# Sheet_1_Main_bord.net
KiCad netlist of a schematic drawn in Altium Designer
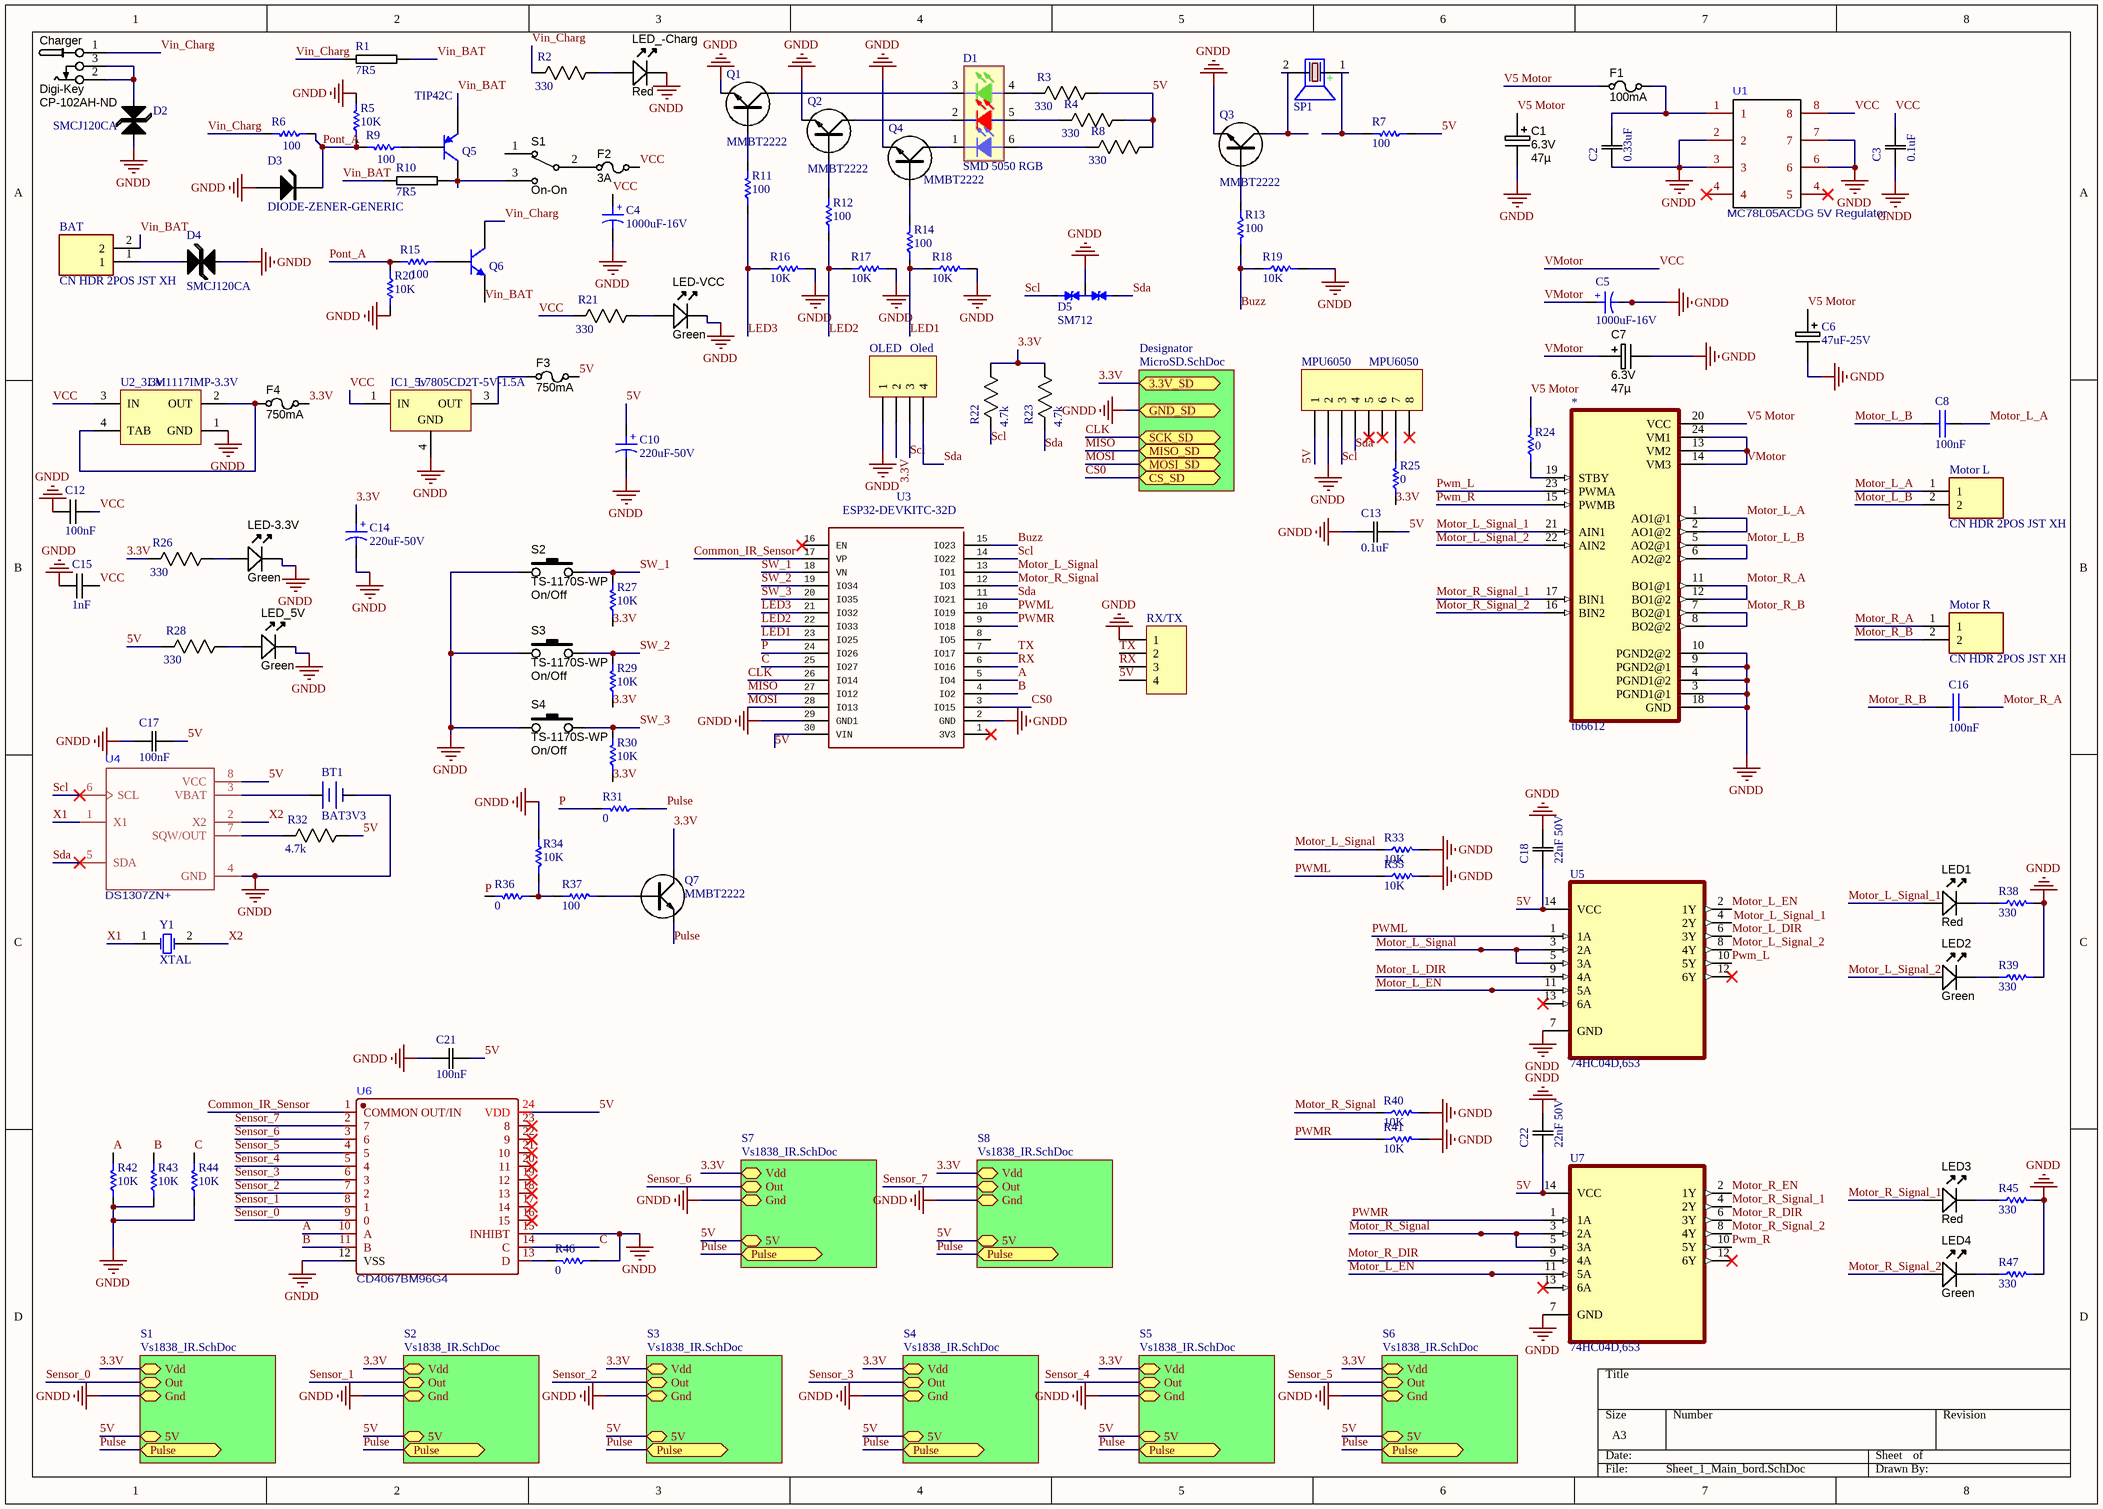
[diagram p0: Sheet_1_Main_bord.SchDoc]

(export (version "E")
  (design (tool "Eeschema 10.0.6"))
  (components
    (comp (ref "*")
      (value "tb6612")
      (footprint "Ssop24_SOP65P760X160-24N")
      (libsource (lib "Schlib_1") (part "tb6612"))
    )
    (comp (ref "BAT")
      (value "CN HDR 2POS JST XH")
      (footprint "JST_B2B-XH-A(LF)(SN)")
      (description "Connector Header Through Hole 2 position 0.098 _2.50mm_\r\nJST XH")
      (fields (field (name "MP") "B2B-XH-A_LF__SN_") (field (name "MF") "JST Sales"))
      (libsource (lib "") (part "CN HDR 2POS JST XH_1"))
    )
    (comp (ref "BT1")
      (value "BAT3V3")
      (footprint "BTH1220")
      (description "Battry Backup")
      (fields (field (name "DESIGNER") "Abbas Basereh"))
      (libsource (lib "Altium") (part "Battry Backup"))
    )
    (comp (ref "C1")
      (value "47µ")
      (footprint "CAPMP3528X210N")
      (description "Capacitor SMD Tantalum 47uF 20% 6.3V 1210")
      (fields (field (name "TOLERANCE") "±20%") (field (name "RATINGS") "6.3V"))
      (libsource (lib "BPL_Library") (part "CAPT_47u_1210_6V3"))
    )
    (comp (ref "C2")
      (value "0.33uF")
      (footprint "0805")
      (description "CAP CER 0.1UF 50V X7R 0805")
      (fields (field (name "TOLERANCE") "10%"))
      (libsource (lib "AltiumLibraries") (part "CAP 470nF 50V"))
    )
    (comp (ref "C3")
      (value "0.1uF")
      (footprint "0805")
      (description "CAP CER 0.1UF 50V X7R 0805")
      (fields (field (name "TOLERANCE") "10%"))
      (libsource (lib "AltiumLibraries") (part "CAP 470nF 50V"))
    )
    (comp (ref "C4")
      (value "1000uF-16V")
      (footprint "CAP SMD 1000UF 16V")
      (description "Cap electrolitic radial")
      (fields (field (name "DESIGNER") "Abbas Basereh"))
      (libsource (lib "Altium") (part "Cap ELECTROLITIC TOTAL SIZE"))
    )
    (comp (ref "C5")
      (value "1000uF-16V")
      (footprint "CAP SMD 1000UF 16V")
      (description "Cap electrolitic radial")
      (fields (field (name "DESIGNER") "Abbas Basereh"))
      (libsource (lib "Altium") (part "Cap ELECTROLITIC TOTAL SIZE"))
    )
    (comp (ref "C6")
      (value "47uF-25V")
      (footprint "PANACAP-D-GENERIC")
      (description "GENERIC CAPACITOR POLARISED")
      (libsource (lib "vh_altium_library") (part "PANACAP-47UF-25V-FK"))
    )
    (comp (ref "C7")
      (value "47µ")
      (footprint "CAPMP3528X210N")
      (description "Capacitor SMD Tantalum 47uF 20% 6.3V 1210")
      (fields (field (name "TOLERANCE") "±20%") (field (name "RATINGS") "6.3V"))
      (libsource (lib "BPL_Library") (part "CAPT_47u_1210_6V3"))
    )
    (comp (ref "C8")
      (value "100nF")
      (footprint "Cap - 100nF - 2")
      (description "Bipolar Capacitor")
      (fields (field (name "VOLTAGE") "100V") (field (name "DESIGNER") "Saeid Jorablo"))
      (libsource (lib "Electrovolt Lib") (part "Cap-Bipolar"))
    )
    (comp (ref "C10")
      (value "220uF-50V")
      (footprint "CAP SMD 1000UF 16V")
      (description "Cap electrolitic radial")
      (fields (field (name "DESIGNER") "Abbas Basereh"))
      (libsource (lib "Altium") (part "Cap ELECTROLITIC TOTAL SIZE"))
    )
    (comp (ref "C12")
      (value "100nF")
      (footprint "1206C-GENERIC")
      (description "CAPACITOR 0603 CERAMIC")
      (libsource (lib "vh_altium_library") (part "1206C-2U2-50V"))
    )
    (comp (ref "C13")
      (value "0.1uF")
      (footprint "0805")
      (description "CAP CER 0.1UF 50V X7R 0805")
      (fields (field (name "TOLERANCE") "10%"))
      (libsource (lib "AltiumLibraries") (part "CAP 470nF 50V"))
    )
    (comp (ref "C14")
      (value "220uF-50V")
      (footprint "CAP SMD 1000UF 16V")
      (description "Cap electrolitic radial")
      (fields (field (name "DESIGNER") "Abbas Basereh"))
      (libsource (lib "Altium") (part "Cap ELECTROLITIC TOTAL SIZE"))
    )
    (comp (ref "C15")
      (value "1nF")
      (footprint "1206C-GENERIC")
      (description "CAPACITOR 0603 CERAMIC")
      (libsource (lib "vh_altium_library") (part "1206C-2U2-50V"))
    )
    (comp (ref "C16")
      (value "100nF")
      (footprint "Cap - 100nF - 2")
      (description "Bipolar Capacitor")
      (fields (field (name "VOLTAGE") "100V") (field (name "DESIGNER") "Saeid Jorablo"))
      (libsource (lib "Electrovolt Lib") (part "Cap-Bipolar"))
    )
    (comp (ref "C17")
      (value "100nF")
      (footprint "0805")
      (description "CAP CER 0.1UF 50V X7R 0805")
      (fields (field (name "TOLERANCE") "10%"))
      (libsource (lib "AltiumLibraries") (part "CAP 470nF 50V"))
    )
    (comp (ref "C18")
      (value "22nF 50V")
      (footprint "0805")
      (description "CAP CER 0.1UF 50V X7R 0805")
      (fields (field (name "TOLERANCE") "10%"))
      (libsource (lib "AltiumLibraries") (part "CAP 470nF 50V"))
    )
    (comp (ref "C21")
      (value "100nF")
      (footprint "0805")
      (description "CAP CER 0.1UF 50V X7R 0805")
      (fields (field (name "TOLERANCE") "10%"))
      (libsource (lib "AltiumLibraries") (part "CAP 470nF 50V"))
    )
    (comp (ref "C22")
      (value "22nF 50V")
      (footprint "0805")
      (description "CAP CER 0.1UF 50V X7R 0805")
      (fields (field (name "TOLERANCE") "10%"))
      (libsource (lib "AltiumLibraries") (part "CAP 470nF 50V"))
    )
    (comp (ref "Charger")
      (value "CONN_PWR_JACK_2.1x5.5mm")
      (footprint "CONN_PWR_JACK_2.1x5.5mm")
      (description "Power Connector, THT, 2.1mm ID, 5.5mm OD")
      (fields (field (name "SUPPLIER 1") "Digi-Key") (field (name "SUPPLIER PART NUMBER 1") "CP-102AH-ND"))
      (libsource (lib "BPL_Library") (part "CONN_PWR_JACK_2.1x5.5mm"))
    )
    (comp (ref "D1")
      (value "probably led colors not mach to real please check the device and change the component")
      (footprint "5050 LED package")
      (description "SMD 5050 RGB LED")
      (fields
        (field (name "COMMENT_1") "SMD 5050 RGB")
        (field (name "DESIGNER") "Abbas Basereh")
        (field (name "PUBLISHER") "Abbas Basereh")
      )
      (libsource (lib "Altium") (part "LED SMD 5050 RGB"))
    )
    (comp (ref "D2")
      (value "SMCJ120CA")
      (footprint "DIODE-SMC")
      (description "Transient Surpression Diode TVS")
      (libsource (lib "vh_altium_library") (part "SMCJ120CA"))
    )
    (comp (ref "D3")
      (value "DIODE-ZENER-GENERIC")
      (footprint "SOT23-DIODE")
      (description "GENERIC ZENER DIODE")
      (libsource (lib "vh_altium_library") (part "DIODE-ZENER-GENERIC"))
    )
    (comp (ref "D4")
      (value "SMCJ120CA")
      (footprint "DIODE-SMC")
      (description "Transient Surpression Diode TVS")
      (libsource (lib "vh_altium_library") (part "SMCJ120CA"))
    )
    (comp (ref "D5")
      (value "SM712")
      (footprint "PSM12___SOT23")
      (description "Asymmetrical TVS Diode for  Extended Common-Mode RS-485")
      (fields (field (name "MANUFACTURER") "SEMTECH") (field (name "MANUFACTURE PART #") "SM712.TC"))
      (libsource (lib "Diode") (part "SM712.TC"))
    )
    (comp (ref "F1")
      (value "100mA")
      (footprint "RESC3216X70N")
      (description "Fuse 160mA 63VDC 1206 SMD")
      (fields (field (name "Comment") "Slow-blow"))
      (libsource (lib "BPL_Library") (part "FUSE_160mA_1206"))
    )
    (comp (ref "F2")
      (value "3A")
      (footprint "RESC3216X70N")
      (description "Fuse 160mA 63VDC 1206 SMD")
      (fields (field (name "Comment") "Slow-blow"))
      (libsource (lib "BPL_Library") (part "FUSE_160mA_1206"))
    )
    (comp (ref "F3")
      (value "750mA")
      (footprint "RESC3216X70N")
      (description "Fuse 160mA 63VDC 1206 SMD")
      (fields (field (name "Comment") "Slow-blow"))
      (libsource (lib "BPL_Library") (part "FUSE_160mA_1206"))
    )
    (comp (ref "F4")
      (value "750mA")
      (footprint "RESC3216X70N")
      (description "Fuse 160mA 63VDC 1206 SMD")
      (fields (field (name "Comment") "Slow-blow"))
      (libsource (lib "BPL_Library") (part "FUSE_160mA_1206"))
    )
    (comp (ref "IC1_5v")
      (value "L7805CD2T-5V-1.5A")
      (footprint "TO-252")
      (description "Precision 500mA Regulator")
      (libsource (lib "Electrovolt Lib") (part "L78M05"))
    )
    (comp (ref "LED-3.3V")
      (value "~")
      (footprint "LED-0805-K")
      (description "LED, 0805 SMD, Green")
      (fields (field (name "COLOR") "Green"))
      (libsource (lib "BPL_Library") (part "LED_SMD_Green_0805_6mcd"))
    )
    (comp (ref "LED-VCC")
      (value "~")
      (footprint "LED-0805-K")
      (description "LED, 0805 SMD, Green")
      (fields (field (name "COLOR") "Green"))
      (libsource (lib "BPL_Library") (part "LED_SMD_Green_0805_6mcd"))
    )
    (comp (ref "LED1")
      (value "~")
      (footprint "LED-0805-K")
      (description "LED 0805 SMD Red 6mcd 621nm")
      (fields (field (name "COLOR") "Red"))
      (libsource (lib "BPL_Library") (part "LED_SMD_Red_0805_6mcd"))
    )
    (comp (ref "LED2")
      (value "~")
      (footprint "LED-0805-K")
      (description "LED, 0805 SMD, Green")
      (fields (field (name "COLOR") "Green"))
      (libsource (lib "BPL_Library") (part "LED_SMD_Green_0805_6mcd"))
    )
    (comp (ref "LED3")
      (value "~")
      (footprint "LED-0805-K")
      (description "LED 0805 SMD Red 6mcd 621nm")
      (fields (field (name "COLOR") "Red"))
      (libsource (lib "BPL_Library") (part "LED_SMD_Red_0805_6mcd"))
    )
    (comp (ref "LED4")
      (value "~")
      (footprint "LED-0805-K")
      (description "LED, 0805 SMD, Green")
      (fields (field (name "COLOR") "Green"))
      (libsource (lib "BPL_Library") (part "LED_SMD_Green_0805_6mcd"))
    )
    (comp (ref "LED_-Charg")
      (value "~")
      (footprint "LED-0805-K")
      (description "LED 0805 SMD Red 6mcd 621nm")
      (fields (field (name "COLOR") "Red"))
      (libsource (lib "BPL_Library") (part "LED_SMD_Red_0805_6mcd"))
    )
    (comp (ref "LED_5V")
      (value "~")
      (footprint "LED-0805-K")
      (description "LED, 0805 SMD, Green")
      (fields (field (name "COLOR") "Green"))
      (libsource (lib "BPL_Library") (part "LED_SMD_Green_0805_6mcd"))
    )
    (comp (ref "Motor L")
      (value "CN HDR 2POS JST XH")
      (footprint "JST_B2B-XH-A(LF)(SN)")
      (description "Connector Header Through Hole 2 position 0.098 _2.50mm_\r\nJST XH")
      (fields (field (name "MP") "B2B-XH-A_LF__SN_") (field (name "MF") "JST Sales"))
      (libsource (lib "AltiumLibraries") (part "CN HDR 2POS JST XH"))
    )
    (comp (ref "Motor R")
      (value "CN HDR 2POS JST XH")
      (footprint "JST_B2B-XH-A(LF)(SN)")
      (description "Connector Header Through Hole 2 position 0.098 _2.50mm_\r\nJST XH")
      (fields (field (name "MP") "B2B-XH-A_LF__SN_") (field (name "MF") "JST Sales"))
      (libsource (lib "AltiumLibraries") (part "CN HDR 2POS JST XH"))
    )
    (comp (ref "MPU6050")
      (value "MPU6050")
      (footprint "HDR1X8")
      (description "Header, 8-Pin")
      (fields (field (name "PUBLISHER") "Altium Limited"))
      (libsource (lib "Altium") (part "Header 8"))
    )
    (comp (ref "OLED")
      (value "Oled")
      (footprint "HDR1X4")
      (description "Header, 4-Pin")
      (fields (field (name "PUBLISHER") "Altium Limited"))
      (libsource (lib "") (part "Header 4_1"))
    )
    (comp (ref "Q1")
      (value "MMBT2222")
      (footprint "SOT23-BCE")
      (description "BC847 SMALL SIGNAL NPN TRANSISTOR")
      (libsource (lib "vh_altium_library") (part "MMBT2222"))
    )
    (comp (ref "Q2")
      (value "MMBT2222")
      (footprint "SOT23-BCE")
      (description "BC847 SMALL SIGNAL NPN TRANSISTOR")
      (libsource (lib "vh_altium_library") (part "MMBT2222"))
    )
    (comp (ref "Q3")
      (value "MMBT2222")
      (footprint "SOT23-BCE")
      (description "BC847 SMALL SIGNAL NPN TRANSISTOR")
      (libsource (lib "vh_altium_library") (part "MMBT2222"))
    )
    (comp (ref "Q4")
      (value "MMBT2222")
      (footprint "SOT23-BCE")
      (description "BC847 SMALL SIGNAL NPN TRANSISTOR")
      (libsource (lib "vh_altium_library") (part "MMBT2222"))
    )
    (comp (ref "Q5")
      (value "TIP42C")
      (footprint "TO-220 AB")
      (description "PNP  power transistor")
      (fields (field (name "MANUFACTURER") "STMicroelectronics") (field (name "DESIGNER") "Abbas Basereh"))
      (libsource (lib "Altium") (part "TIP42C"))
    )
    (comp (ref "Q6")
      (value "TIP41C")
      (footprint "TO-220 AB")
      (description "NPN  power transistor")
      (fields (field (name "MANUFACTURER") "STMicroelectronics") (field (name "DESIGNER") "Abbas Basereh"))
      (libsource (lib "Altium") (part "TIP41C"))
    )
    (comp (ref "Q7")
      (value "MMBT2222")
      (footprint "SOT23-BCE")
      (description "BC847 SMALL SIGNAL NPN TRANSISTOR")
      (libsource (lib "vh_altium_library") (part "MMBT2222"))
    )
    (comp (ref "R1")
      (value "7R5")
      (footprint "2512R-GENERIC")
      (description "GENERIC RESISTOR 2512")
      (fields
        (field (name "MANUFACTURER PART NUMBER") "CRCW25127R50JNEG")
        (field (name "MANUFACTURER") "Vishay/Dale")
      )
      (libsource (lib "vh_altium_library") (part "2512R-7R5"))
    )
    (comp (ref "R2")
      (value "330")
      (footprint "0805")
      (description "RES SMD 1K OHM 1% 1/8W 0603/0805")
      (fields (field (name "TOLERANCE") "1%"))
      (libsource (lib "AltiumLibraries") (part "RES 1k 1/8W - 1%"))
    )
    (comp (ref "R3")
      (value "330")
      (footprint "0805")
      (description "RES SMD 330 OHM 1% 1/8W 0805")
      (fields (field (name "TOLERANCE") "1%"))
      (libsource (lib "AltiumLibraries") (part "RES 330.0 1/8W - 1%"))
    )
    (comp (ref "R4")
      (value "330")
      (footprint "0805")
      (description "RES SMD 330 OHM 1% 1/8W 0805")
      (fields (field (name "TOLERANCE") "1%"))
      (libsource (lib "AltiumLibraries") (part "RES 330.0 1/8W - 1%"))
    )
    (comp (ref "R5")
      (value "10K")
      (footprint "RES 0805 (2012X06L)")
      (description "Resistor")
      (fields (field (name "TOLERANCE") "5%") (field (name "POWER") "1/8 W"))
      (libsource (lib "Electrovolt Lib") (part "Resistor"))
    )
    (comp (ref "R6")
      (value "100")
      (footprint "RES 0805 (2012X06L)")
      (description "Resistor")
      (fields (field (name "TOLERANCE") "5%") (field (name "POWER") "1/8 W"))
      (libsource (lib "Electrovolt Lib") (part "Resistor"))
    )
    (comp (ref "R7")
      (value "100")
      (footprint "RES 0805 (2012X06L)")
      (description "Resistor")
      (fields (field (name "TOLERANCE") "5%") (field (name "POWER") "1/8 W"))
      (libsource (lib "Electrovolt Lib") (part "Resistor"))
    )
    (comp (ref "R8")
      (value "330")
      (footprint "0805")
      (description "RES SMD 330 OHM 1% 1/8W 0805")
      (fields (field (name "TOLERANCE") "1%"))
      (libsource (lib "AltiumLibraries") (part "RES 330.0 1/8W - 1%"))
    )
    (comp (ref "R9")
      (value "100")
      (footprint "RES 0805 (2012X06L)")
      (description "Resistor")
      (fields (field (name "TOLERANCE") "5%") (field (name "POWER") "1/8 W"))
      (libsource (lib "Electrovolt Lib") (part "Resistor"))
    )
    (comp (ref "R10")
      (value "7R5")
      (footprint "2512R-GENERIC")
      (description "GENERIC RESISTOR 2512")
      (fields
        (field (name "MANUFACTURER PART NUMBER") "CRCW25127R50JNEG")
        (field (name "MANUFACTURER") "Vishay/Dale")
      )
      (libsource (lib "vh_altium_library") (part "2512R-7R5"))
    )
    (comp (ref "R11")
      (value "100")
      (footprint "RES 0805 (2012X06L)")
      (description "Resistor")
      (fields (field (name "TOLERANCE") "5%") (field (name "POWER") "1/8 W"))
      (libsource (lib "Electrovolt Lib") (part "Resistor"))
    )
    (comp (ref "R12")
      (value "100")
      (footprint "RES 0805 (2012X06L)")
      (description "Resistor")
      (fields (field (name "TOLERANCE") "5%") (field (name "POWER") "1/8 W"))
      (libsource (lib "Electrovolt Lib") (part "Resistor"))
    )
    (comp (ref "R13")
      (value "100")
      (footprint "RES 0805 (2012X06L)")
      (description "Resistor")
      (fields (field (name "TOLERANCE") "5%") (field (name "POWER") "1/8 W"))
      (libsource (lib "Electrovolt Lib") (part "Resistor"))
    )
    (comp (ref "R14")
      (value "100")
      (footprint "RES 0805 (2012X06L)")
      (description "Resistor")
      (fields (field (name "TOLERANCE") "5%") (field (name "POWER") "1/8 W"))
      (libsource (lib "Electrovolt Lib") (part "Resistor"))
    )
    (comp (ref "R15")
      (value "100")
      (footprint "RES 0805 (2012X06L)")
      (description "Resistor")
      (fields (field (name "TOLERANCE") "5%") (field (name "POWER") "1/8 W"))
      (libsource (lib "Electrovolt Lib") (part "Resistor"))
    )
    (comp (ref "R16")
      (value "10K")
      (footprint "RES 0805 (2012X06L)")
      (description "Resistor")
      (fields (field (name "TOLERANCE") "5%") (field (name "POWER") "1/8 W"))
      (libsource (lib "Electrovolt Lib") (part "Resistor"))
    )
    (comp (ref "R17")
      (value "10K")
      (footprint "RES 0805 (2012X06L)")
      (description "Resistor")
      (fields (field (name "TOLERANCE") "5%") (field (name "POWER") "1/8 W"))
      (libsource (lib "Electrovolt Lib") (part "Resistor"))
    )
    (comp (ref "R18")
      (value "10K")
      (footprint "RES 0805 (2012X06L)")
      (description "Resistor")
      (fields (field (name "TOLERANCE") "5%") (field (name "POWER") "1/8 W"))
      (libsource (lib "Electrovolt Lib") (part "Resistor"))
    )
    (comp (ref "R19")
      (value "10K")
      (footprint "RES 0805 (2012X06L)")
      (description "Resistor")
      (fields (field (name "TOLERANCE") "5%") (field (name "POWER") "1/8 W"))
      (libsource (lib "Electrovolt Lib") (part "Resistor"))
    )
    (comp (ref "R20")
      (value "10K")
      (footprint "RES 0805 (2012X06L)")
      (description "Resistor")
      (fields (field (name "TOLERANCE") "5%") (field (name "POWER") "1/8 W"))
      (libsource (lib "Electrovolt Lib") (part "Resistor"))
    )
    (comp (ref "R21")
      (value "330")
      (footprint "0805")
      (description "RES SMD 330 OHM 1% 1/8W 0805")
      (fields (field (name "TOLERANCE") "1%"))
      (libsource (lib "AltiumLibraries") (part "RES 330.0 1/8W - 1%"))
    )
    (comp (ref "R22")
      (value "4.7k")
      (footprint "0805")
      (description "RES SMD 4.7k OHM 5% 1/8W 0805")
      (fields (field (name "TOLERANCE") "5%"))
      (libsource (lib "AltiumLibraries") (part "RES 4.7k 1/8W - 5%"))
    )
    (comp (ref "R23")
      (value "4.7k")
      (footprint "0805")
      (description "RES SMD 4.7k OHM 5% 1/8W 0805")
      (fields (field (name "TOLERANCE") "5%"))
      (libsource (lib "AltiumLibraries") (part "RES 4.7k 1/8W - 5%"))
    )
    (comp (ref "R24")
      (value "0")
      (footprint "SMD_RES_0805")
      (description "Resistor")
      (fields (field (name "TOLERANCE") "5%") (field (name "POWER") "1/8 W"))
      (libsource (lib "Electrovolt Lib") (part "Resistor"))
    )
    (comp (ref "R25")
      (value "0")
      (footprint "SMD_RES_0805")
      (description "Resistor")
      (fields (field (name "TOLERANCE") "5%") (field (name "POWER") "1/8 W"))
      (libsource (lib "Electrovolt Lib") (part "Resistor"))
    )
    (comp (ref "R26")
      (value "330")
      (footprint "0805")
      (description "RES SMD 330 OHM 1% 1/8W 0805")
      (fields (field (name "TOLERANCE") "1%"))
      (libsource (lib "AltiumLibraries") (part "RES 330.0 1/8W - 1%"))
    )
    (comp (ref "R27")
      (value "10K")
      (footprint "RES 0805 (2012X06L)")
      (description "Resistor")
      (fields (field (name "TOLERANCE") "5%") (field (name "POWER") "1/8 W"))
      (libsource (lib "Electrovolt Lib") (part "Resistor"))
    )
    (comp (ref "R28")
      (value "330")
      (footprint "0805")
      (description "RES SMD 330 OHM 1% 1/8W 0805")
      (fields (field (name "TOLERANCE") "1%"))
      (libsource (lib "AltiumLibraries") (part "RES 330.0 1/8W - 1%"))
    )
    (comp (ref "R29")
      (value "10K")
      (footprint "RES 0805 (2012X06L)")
      (description "Resistor")
      (fields (field (name "TOLERANCE") "5%") (field (name "POWER") "1/8 W"))
      (libsource (lib "Electrovolt Lib") (part "Resistor"))
    )
    (comp (ref "R30")
      (value "10K")
      (footprint "RES 0805 (2012X06L)")
      (description "Resistor")
      (fields (field (name "TOLERANCE") "5%") (field (name "POWER") "1/8 W"))
      (libsource (lib "Electrovolt Lib") (part "Resistor"))
    )
    (comp (ref "R31")
      (value "0")
      (footprint "RES 0805 (2012X06L)")
      (description "Resistor")
      (fields (field (name "TOLERANCE") "5%") (field (name "POWER") "1/8 W"))
      (libsource (lib "Electrovolt Lib") (part "Resistor"))
    )
    (comp (ref "R32")
      (value "4.7k")
      (footprint "0805")
      (description "RES SMD 4.7k OHM 5% 1/8W 0805")
      (fields (field (name "TOLERANCE") "5%"))
      (libsource (lib "AltiumLibraries") (part "RES 4.7k 1/8W - 5%"))
    )
    (comp (ref "R33")
      (value "10K")
      (footprint "RES 0805 (2012X06L)")
      (description "Resistor")
      (fields (field (name "TOLERANCE") "5%") (field (name "POWER") "1/8 W"))
      (libsource (lib "Electrovolt Lib") (part "Resistor"))
    )
    (comp (ref "R34")
      (value "10K")
      (footprint "RES 0805 (2012X06L)")
      (description "Resistor")
      (fields (field (name "TOLERANCE") "5%") (field (name "POWER") "1/8 W"))
      (libsource (lib "Electrovolt Lib") (part "Resistor"))
    )
    (comp (ref "R35")
      (value "10K")
      (footprint "RES 0805 (2012X06L)")
      (description "Resistor")
      (fields (field (name "TOLERANCE") "5%") (field (name "POWER") "1/8 W"))
      (libsource (lib "Electrovolt Lib") (part "Resistor"))
    )
    (comp (ref "R36")
      (value "0")
      (footprint "RES 0805 (2012X06L)")
      (description "Resistor")
      (fields (field (name "TOLERANCE") "5%") (field (name "POWER") "1/8 W"))
      (libsource (lib "Electrovolt Lib") (part "Resistor"))
    )
    (comp (ref "R37")
      (value "100")
      (footprint "RES 0805 (2012X06L)")
      (description "Resistor")
      (fields (field (name "TOLERANCE") "5%") (field (name "POWER") "1/8 W"))
      (libsource (lib "Electrovolt Lib") (part "Resistor"))
    )
    (comp (ref "R38")
      (value "330")
      (footprint "RES 0805 (2012X06L)")
      (description "Resistor")
      (fields (field (name "TOLERANCE") "5%") (field (name "POWER") "1/8 W"))
      (libsource (lib "Electrovolt Lib") (part "Resistor"))
    )
    (comp (ref "R39")
      (value "330")
      (footprint "RES 0805 (2012X06L)")
      (description "Resistor")
      (fields (field (name "TOLERANCE") "5%") (field (name "POWER") "1/8 W"))
      (libsource (lib "Electrovolt Lib") (part "Resistor"))
    )
    (comp (ref "R40")
      (value "10K")
      (footprint "RES 0805 (2012X06L)")
      (description "Resistor")
      (fields (field (name "TOLERANCE") "5%") (field (name "POWER") "1/8 W"))
      (libsource (lib "Electrovolt Lib") (part "Resistor"))
    )
    (comp (ref "R41")
      (value "10K")
      (footprint "RES 0805 (2012X06L)")
      (description "Resistor")
      (fields (field (name "TOLERANCE") "5%") (field (name "POWER") "1/8 W"))
      (libsource (lib "Electrovolt Lib") (part "Resistor"))
    )
    (comp (ref "R42")
      (value "10K")
      (footprint "RES 0805 (2012X06L)")
      (description "Resistor")
      (fields (field (name "TOLERANCE") "5%") (field (name "POWER") "1/8 W"))
      (libsource (lib "Electrovolt Lib") (part "Resistor"))
    )
    (comp (ref "R43")
      (value "10K")
      (footprint "RES 0805 (2012X06L)")
      (description "Resistor")
      (fields (field (name "TOLERANCE") "5%") (field (name "POWER") "1/8 W"))
      (libsource (lib "Electrovolt Lib") (part "Resistor"))
    )
    (comp (ref "R44")
      (value "10K")
      (footprint "RES 0805 (2012X06L)")
      (description "Resistor")
      (fields (field (name "TOLERANCE") "5%") (field (name "POWER") "1/8 W"))
      (libsource (lib "Electrovolt Lib") (part "Resistor"))
    )
    (comp (ref "R45")
      (value "330")
      (footprint "RES 0805 (2012X06L)")
      (description "Resistor")
      (fields (field (name "TOLERANCE") "5%") (field (name "POWER") "1/8 W"))
      (libsource (lib "Electrovolt Lib") (part "Resistor"))
    )
    (comp (ref "R46")
      (value "0")
      (footprint "RES 0805 (2012X06L)")
      (description "Resistor")
      (fields (field (name "TOLERANCE") "5%") (field (name "POWER") "1/8 W"))
      (libsource (lib "Electrovolt Lib") (part "Resistor"))
    )
    (comp (ref "R47")
      (value "330")
      (footprint "RES 0805 (2012X06L)")
      (description "Resistor")
      (fields (field (name "TOLERANCE") "5%") (field (name "POWER") "1/8 W"))
      (libsource (lib "Electrovolt Lib") (part "Resistor"))
    )
    (comp (ref "RX/TX")
      (value "~")
      (footprint "HDR1X4")
      (description "Header, 4-Pin")
      (fields (field (name "PUBLISHER") "Altium Limited"))
      (libsource (lib "Altium") (part "Header 4"))
    )
    (comp (ref "S1")
      (value "ON-ON")
      (footprint "SWITCH_SPDT_SLIDER")
      (description "Switch THD vertical toggle SPDT")
      (fields (field (name "SWITCH FUNCTION") "On-On"))
      (libsource (lib "BPL_Library") (part "SW_THD_SPDT_On-On"))
    )
    (comp (ref "S2")
      (value "TS-1170S-WP")
      (footprint "TS-1170S")
      (description "Switch SMD Tact 7.0mm Stem")
      (fields (field (name "FUNCTION") "On/Off"))
      (libsource (lib "BPL_Library") (part "SW_SMD_PB_7.0mm"))
    )
    (comp (ref "S3")
      (value "TS-1170S-WP")
      (footprint "TS-1170S")
      (description "Switch SMD Tact 7.0mm Stem")
      (fields (field (name "FUNCTION") "On/Off"))
      (libsource (lib "BPL_Library") (part "SW_SMD_PB_7.0mm"))
    )
    (comp (ref "S4")
      (value "TS-1170S-WP")
      (footprint "TS-1170S")
      (description "Switch SMD Tact 7.0mm Stem")
      (fields (field (name "FUNCTION") "On/Off"))
      (libsource (lib "BPL_Library") (part "SW_SMD_PB_7.0mm"))
    )
    (comp (ref "SP1")
      (value "~")
      (footprint "BUZZER 7.62mm DC")
      (description "PIEZO BUZZER ACTIVE")
      (fields (field (name "DESIGNER") "Abbas Basereh") (field (name "PUBLISHER") "Abbas Basereh"))
      (libsource (lib "Altium") (part "PIEZO BUZZER"))
    )
    (comp (ref "U1")
      (value "MC78L05ACDG 5V Regulator")
      (footprint "78L05CD15V5V_LIB")
      (libsource (lib "Schlib_1") (part "MC78L05ACDG 5V Regulator"))
    )
    (comp (ref "U2_3.3v")
      (value "LM1117IMP-3.3V")
      (footprint "TO-252")
      (description "x.x Volt, 800mA Low-Dropout Linear Regulator, 4-pin SOT-223")
      (fields
        (field (name "PARTNUMBER") "LM1117IMP-3.3")
        (field (name "MANUFACTURER") "National Semiconductor")
        (field (name "PUBLISHER") "Altium Limited")
      )
      (libsource (lib "Electrovolt Lib") (part "LM1117IMP-x.x"))
    )
    (comp (ref "U3")
      (value "ESP32-DEVKITC-32D")
      (footprint "MODULE_ESP32-DEVKITV1")
      (description "Eval Board For Esp-Wroom-32")
      (fields (field (name "MF") "Espressif Systems"))
      (libsource (lib "Integrated_Library12") (part "ESP32-DEVKITC-32D"))
    )
    (comp (ref "U4") (value "DS1307ZN+") (footprint "SOIC-8") (libsource (lib "Schlib_1") (part "DS1307ZN+")))
    (comp (ref "U5")
      (value "74HC04D,653")
      (footprint "SOIC127P600X175-14AN")
      (description "Inverter IC 6 Channel 14-SO")
      (fields (field (name "MF") "Nexperia USA"))
      (libsource (lib "74HC04D_653") (part "74HC04D,653"))
    )
    (comp (ref "U6")
      (value "CD4067BM96G4")
      (footprint "CD4067BM_SOIC-24")
      (libsource (lib "Schlib_1") (part "CD4067BM96G4"))
    )
    (comp (ref "U7")
      (value "74HC04D,653")
      (footprint "SOIC127P600X175-14AN")
      (description "Inverter IC 6 Channel 14-SO")
      (fields (field (name "MF") "Nexperia USA"))
      (libsource (lib "74HC04D_653") (part "74HC04D,653"))
    )
    (comp (ref "Y1")
      (value "XTAL")
      (footprint "R38")
      (description "Crystal Oscillator")
      (fields (field (name "PUBLISHER") "Altium Limited"))
      (libsource (lib "Miscellaneous Devices") (part "XTAL"))
    )
  )
  (nets
    (net (code "1") (name "/3.3V") (class "Default")
      (node (ref "C14") (pin "1") (pinfunction "1_1") (pintype "passive"))
      (node (ref "F4") (pin "1") (pinfunction "1_1") (pintype "passive"))
      (node (ref "OLED") (pin "2") (pinfunction "2_2") (pintype "passive"))
      (node (ref "Q7") (pin "C") (pintype "passive"))
      (node (ref "R22") (pin "1") (pinfunction "R1_1") (pintype "passive"))
      (node (ref "R23") (pin "1") (pinfunction "R1_1") (pintype "passive"))
      (node (ref "R25") (pin "1") (pinfunction "1_1") (pintype "passive"))
      (node (ref "R26") (pin "2") (pinfunction "R2_2") (pintype "passive"))
      (node (ref "R27") (pin "1") (pinfunction "1_1") (pintype "passive"))
      (node (ref "R29") (pin "1") (pinfunction "1_1") (pintype "passive"))
      (node (ref "R30") (pin "1") (pinfunction "1_1") (pintype "passive"))
    )
    (net (code "2") (name "/5V") (class "Default")
      (node (ref "C10") (pin "1") (pinfunction "1_1") (pintype "passive"))
      (node (ref "C13") (pin "2") (pinfunction "C2_2") (pintype "passive"))
      (node (ref "C17") (pin "2") (pinfunction "C2_2") (pintype "passive"))
      (node (ref "C18") (pin "1") (pinfunction "C1_1") (pintype "passive"))
      (node (ref "C21") (pin "2") (pinfunction "C2_2") (pintype "passive"))
      (node (ref "C22") (pin "1") (pinfunction "C1_1") (pintype "passive"))
      (node (ref "F3") (pin "1") (pinfunction "1_1") (pintype "passive"))
      (node (ref "MPU6050") (pin "1") (pinfunction "1_1") (pintype "passive"))
      (node (ref "R28") (pin "2") (pinfunction "R2_2") (pintype "passive"))
      (node (ref "R3") (pin "1") (pinfunction "R1_1") (pintype "passive"))
      (node (ref "R32") (pin "1") (pinfunction "R1_1") (pintype "passive"))
      (node (ref "R4") (pin "1") (pinfunction "R1_1") (pintype "passive"))
      (node (ref "R7") (pin "1") (pinfunction "1_1") (pintype "passive"))
      (node (ref "R8") (pin "1") (pinfunction "R1_1") (pintype "passive"))
      (node (ref "RX/TX") (pin "4") (pinfunction "4_4") (pintype "passive"))
      (node (ref "U3") (pin "30") (pinfunction "VIN_30") (pintype "passive"))
      (node (ref "U4") (pin "8") (pinfunction "VCC_8") (pintype "passive"))
      (node (ref "U5") (pin "14") (pinfunction "VCC_14") (pintype "power_in"))
      (node (ref "U6") (pin "24") (pinfunction "VDD_24") (pintype "passive"))
      (node (ref "U7") (pin "14") (pinfunction "VCC_14") (pintype "power_in"))
    )
    (net (code "3") (name "/A") (class "Default")
      (node (ref "R42") (pin "2") (pinfunction "2_2") (pintype "passive"))
      (node (ref "U3") (pin "5") (pinfunction "IO4_5") (pintype "passive"))
      (node (ref "U6") (pin "10") (pinfunction "A_10") (pintype "passive"))
    )
    (net (code "4") (name "/B") (class "Default")
      (node (ref "R43") (pin "2") (pinfunction "2_2") (pintype "passive"))
      (node (ref "U3") (pin "4") (pinfunction "IO2_4") (pintype "passive"))
      (node (ref "U6") (pin "11") (pinfunction "B_11") (pintype "passive"))
    )
    (net (code "5") (name "/Buzz") (class "Default")
      (node (ref "R13") (pin "2") (pinfunction "2_2") (pintype "passive"))
      (node (ref "R19") (pin "1") (pinfunction "1_1") (pintype "passive"))
      (node (ref "U3") (pin "15") (pinfunction "IO23_15") (pintype "passive"))
    )
    (net (code "6") (name "/C") (class "Default")
      (node (ref "R44") (pin "2") (pinfunction "2_2") (pintype "passive"))
      (node (ref "U3") (pin "25") (pinfunction "IO27_25") (pintype "passive"))
      (node (ref "U6") (pin "14") (pinfunction "C_14") (pintype "passive"))
    )
    (net (code "7") (name "/CLK") (class "Default")
      (node (ref "U3") (pin "26") (pinfunction "IO14_26") (pintype "passive"))
    )
    (net (code "8") (name "/CS0") (class "Default")
      (node (ref "U3") (pin "3") (pinfunction "IO15_3") (pintype "passive"))
    )
    (net (code "9") (name "/Common_IR_Sensor") (class "Default")
      (node (ref "U3") (pin "17") (pinfunction "VP_17") (pintype "passive"))
      (node (ref "U6") (pin "1") (pinfunction "COMMON_OUT/IN_1") (pintype "passive"))
    )
    (net (code "10") (name "/LED1") (class "Default")
      (node (ref "R14") (pin "1") (pinfunction "1_1") (pintype "passive"))
      (node (ref "R18") (pin "1") (pinfunction "1_1") (pintype "passive"))
      (node (ref "U3") (pin "23") (pinfunction "IO25_23") (pintype "passive"))
    )
    (net (code "11") (name "/LED2") (class "Default")
      (node (ref "R12") (pin "1") (pinfunction "1_1") (pintype "passive"))
      (node (ref "R17") (pin "1") (pinfunction "1_1") (pintype "passive"))
      (node (ref "U3") (pin "22") (pinfunction "IO33_22") (pintype "passive"))
    )
    (net (code "12") (name "/LED3") (class "Default")
      (node (ref "R11") (pin "1") (pinfunction "1_1") (pintype "passive"))
      (node (ref "R16") (pin "1") (pinfunction "1_1") (pintype "passive"))
      (node (ref "U3") (pin "21") (pinfunction "IO32_21") (pintype "passive"))
    )
    (net (code "13") (name "/MISO") (class "Default")
      (node (ref "U3") (pin "27") (pinfunction "IO12_27") (pintype "passive"))
    )
    (net (code "14") (name "/MOSI") (class "Default")
      (node (ref "U3") (pin "28") (pinfunction "IO13_28") (pintype "passive"))
    )
    (net (code "15") (name "/Motor_L_A") (class "Default")
      (node (ref "*") (pin "1") (pinfunction "AO1@1_1") (pintype "output"))
      (node (ref "*") (pin "2") (pinfunction "AO1@2_2") (pintype "output"))
      (node (ref "C8") (pin "2") (pinfunction "-_2") (pintype "passive"))
      (node (ref "Motor L") (pin "1") (pinfunction "1_1") (pintype "passive"))
    )
    (net (code "16") (name "/Motor_L_B") (class "Default")
      (node (ref "*") (pin "5") (pinfunction "AO2@1_5") (pintype "output"))
      (node (ref "*") (pin "6") (pinfunction "AO2@2_6") (pintype "output"))
      (node (ref "C8") (pin "1") (pinfunction "+_1") (pintype "passive"))
      (node (ref "Motor L") (pin "2") (pinfunction "2_2") (pintype "passive"))
    )
    (net (code "17") (name "/Motor_L_DIR") (class "Default")
      (node (ref "U5") (pin "6") (pinfunction "3Y_6") (pintype "output"))
      (node (ref "U5") (pin "9") (pinfunction "4A_9") (pintype "input"))
    )
    (net (code "18") (name "/Motor_L_EN") (class "Default")
      (node (ref "U5") (pin "11") (pinfunction "5A_11") (pintype "input"))
      (node (ref "U5") (pin "2") (pinfunction "1Y_2") (pintype "output"))
      (node (ref "U7") (pin "11") (pinfunction "5A_11") (pintype "input"))
    )
    (net (code "19") (name "/Motor_L_Signal") (class "Default")
      (node (ref "R33") (pin "1") (pinfunction "1_1") (pintype "passive"))
      (node (ref "U3") (pin "13") (pinfunction "IO1_13") (pintype "passive"))
      (node (ref "U5") (pin "3") (pinfunction "2A_3") (pintype "input"))
      (node (ref "U5") (pin "5") (pinfunction "3A_5") (pintype "input"))
    )
    (net (code "20") (name "/Motor_L_Signal_1") (class "Default")
      (node (ref "*") (pin "21") (pinfunction "AIN1_21") (pintype "input"))
      (node (ref "LED1") (pin "A") (pinfunction "A_A") (pintype "passive"))
    )
    (net (code "21") (name "/Motor_L_Signal_2") (class "Default")
      (node (ref "*") (pin "22") (pinfunction "AIN2_22") (pintype "input"))
      (node (ref "LED2") (pin "A") (pinfunction "A_A") (pintype "passive"))
      (node (ref "U5") (pin "8") (pinfunction "4Y_8") (pintype "output"))
    )
    (net (code "22") (name "/Motor_R_A") (class "Default")
      (node (ref "*") (pin "11") (pinfunction "BO1@1_11") (pintype "output"))
      (node (ref "*") (pin "12") (pinfunction "BO1@2_12") (pintype "output"))
      (node (ref "C16") (pin "2") (pinfunction "-_2") (pintype "passive"))
      (node (ref "Motor R") (pin "1") (pinfunction "1_1") (pintype "passive"))
    )
    (net (code "23") (name "/Motor_R_B") (class "Default")
      (node (ref "*") (pin "7") (pinfunction "BO2@1_7") (pintype "output"))
      (node (ref "*") (pin "8") (pinfunction "BO2@2_8") (pintype "output"))
      (node (ref "C16") (pin "1") (pinfunction "+_1") (pintype "passive"))
      (node (ref "Motor R") (pin "2") (pinfunction "2_2") (pintype "passive"))
    )
    (net (code "24") (name "/Motor_R_DIR") (class "Default")
      (node (ref "U7") (pin "6") (pinfunction "3Y_6") (pintype "output"))
      (node (ref "U7") (pin "9") (pinfunction "4A_9") (pintype "input"))
    )
    (net (code "25") (name "/Motor_R_EN") (class "Default")
      (node (ref "U7") (pin "2") (pinfunction "1Y_2") (pintype "output"))
    )
    (net (code "26") (name "/Motor_R_Signal") (class "Default")
      (node (ref "R40") (pin "1") (pinfunction "1_1") (pintype "passive"))
      (node (ref "U3") (pin "12") (pinfunction "IO3_12") (pintype "passive"))
      (node (ref "U7") (pin "3") (pinfunction "2A_3") (pintype "input"))
      (node (ref "U7") (pin "5") (pinfunction "3A_5") (pintype "input"))
    )
    (net (code "27") (name "/Motor_R_Signal_1") (class "Default")
      (node (ref "*") (pin "17") (pinfunction "BIN1_17") (pintype "input"))
      (node (ref "LED3") (pin "A") (pinfunction "A_A") (pintype "passive"))
      (node (ref "U7") (pin "4") (pinfunction "2Y_4") (pintype "output"))
    )
    (net (code "28") (name "/Motor_R_Signal_2") (class "Default")
      (node (ref "*") (pin "16") (pinfunction "BIN2_16") (pintype "input"))
      (node (ref "LED4") (pin "A") (pinfunction "A_A") (pintype "passive"))
      (node (ref "U7") (pin "8") (pinfunction "4Y_8") (pintype "output"))
    )
    (net (code "29") (name "/P") (class "Default")
      (node (ref "R31") (pin "2") (pinfunction "2_2") (pintype "passive"))
      (node (ref "R36") (pin "2") (pinfunction "2_2") (pintype "passive"))
      (node (ref "U3") (pin "24") (pinfunction "IO26_24") (pintype "passive"))
    )
    (net (code "30") (name "/PWML") (class "Default")
      (node (ref "R35") (pin "1") (pinfunction "1_1") (pintype "passive"))
      (node (ref "U3") (pin "10") (pinfunction "IO19_10") (pintype "passive"))
      (node (ref "U5") (pin "1") (pinfunction "1A_1") (pintype "input"))
    )
    (net (code "31") (name "/PWMR") (class "Default")
      (node (ref "R41") (pin "1") (pinfunction "1_1") (pintype "passive"))
      (node (ref "U3") (pin "9") (pinfunction "IO18_9") (pintype "passive"))
      (node (ref "U7") (pin "1") (pinfunction "1A_1") (pintype "input"))
    )
    (net (code "32") (name "/Pont_A") (class "Default")
      (node (ref "D3") (pin "K") (pinfunction "K_K") (pintype "passive"))
      (node (ref "R15") (pin "2") (pinfunction "2_2") (pintype "passive"))
      (node (ref "R20") (pin "1") (pinfunction "1_1") (pintype "passive"))
      (node (ref "R5") (pin "1") (pinfunction "1_1") (pintype "passive"))
      (node (ref "R6") (pin "1") (pinfunction "1_1") (pintype "passive"))
      (node (ref "R9") (pin "2") (pinfunction "2_2") (pintype "passive"))
    )
    (net (code "33") (name "/Pulse") (class "Default")
      (node (ref "Q7") (pin "E") (pintype "passive"))
      (node (ref "R31") (pin "1") (pinfunction "1_1") (pintype "passive"))
    )
    (net (code "34") (name "/Pwm_L") (class "Default")
      (node (ref "*") (pin "23") (pinfunction "PWMA_23") (pintype "input"))
      (node (ref "U5") (pin "10") (pinfunction "5Y_10") (pintype "output"))
    )
    (net (code "35") (name "/Pwm_R") (class "Default")
      (node (ref "*") (pin "15") (pinfunction "PWMB_15") (pintype "input"))
      (node (ref "U7") (pin "10") (pinfunction "5Y_10") (pintype "output"))
    )
    (net (code "36") (name "/RX") (class "Default")
      (node (ref "RX/TX") (pin "3") (pinfunction "3_3") (pintype "passive"))
      (node (ref "U3") (pin "6") (pinfunction "IO16_6") (pintype "passive"))
    )
    (net (code "37") (name "/SW_1") (class "Default")
      (node (ref "R27") (pin "2") (pinfunction "2_2") (pintype "passive"))
      (node (ref "S2") (pin "2") (pintype "passive"))
      (node (ref "U3") (pin "18") (pinfunction "VN_18") (pintype "passive"))
    )
    (net (code "38") (name "/SW_2") (class "Default")
      (node (ref "R29") (pin "2") (pinfunction "2_2") (pintype "passive"))
      (node (ref "S3") (pin "2") (pintype "passive"))
      (node (ref "U3") (pin "19") (pinfunction "IO34_19") (pintype "passive"))
    )
    (net (code "39") (name "/SW_3") (class "Default")
      (node (ref "R30") (pin "2") (pinfunction "2_2") (pintype "passive"))
      (node (ref "S4") (pin "2") (pintype "passive"))
      (node (ref "U3") (pin "20") (pinfunction "IO35_20") (pintype "passive"))
    )
    (net (code "40") (name "/Scl") (class "Default")
      (node (ref "D5") (pin "1") (pinfunction "1_1") (pintype "passive"))
      (node (ref "MPU6050") (pin "3") (pinfunction "3_3") (pintype "passive"))
      (node (ref "OLED") (pin "3") (pinfunction "3_3") (pintype "passive"))
      (node (ref "R22") (pin "2") (pinfunction "R2_2") (pintype "passive"))
      (node (ref "U3") (pin "14") (pinfunction "IO22_14") (pintype "passive"))
      (node (ref "U4") (pin "6") (pinfunction "SCL_6") (pintype "passive"))
    )
    (net (code "41") (name "/Sda") (class "Default")
      (node (ref "D5") (pin "2") (pinfunction "2_2") (pintype "passive"))
      (node (ref "MPU6050") (pin "4") (pinfunction "4_4") (pintype "passive"))
      (node (ref "OLED") (pin "4") (pinfunction "4_4") (pintype "passive"))
      (node (ref "R23") (pin "2") (pinfunction "R2_2") (pintype "passive"))
      (node (ref "U3") (pin "11") (pinfunction "IO21_11") (pintype "passive"))
      (node (ref "U4") (pin "5") (pinfunction "SDA_5") (pintype "passive"))
    )
    (net (code "42") (name "/Sensor_0") (class "Default")
      (node (ref "U6") (pin "9") (pinfunction "0_9") (pintype "passive"))
    )
    (net (code "43") (name "/Sensor_1") (class "Default")
      (node (ref "U6") (pin "8") (pinfunction "1_8") (pintype "passive"))
    )
    (net (code "44") (name "/Sensor_2") (class "Default")
      (node (ref "U6") (pin "7") (pinfunction "2_7") (pintype "passive"))
    )
    (net (code "45") (name "/Sensor_3") (class "Default")
      (node (ref "U6") (pin "6") (pinfunction "3_6") (pintype "passive"))
    )
    (net (code "46") (name "/Sensor_4") (class "Default")
      (node (ref "U6") (pin "5") (pinfunction "4_5") (pintype "passive"))
    )
    (net (code "47") (name "/Sensor_5") (class "Default")
      (node (ref "U6") (pin "4") (pinfunction "5_4") (pintype "passive"))
    )
    (net (code "48") (name "/Sensor_6") (class "Default")
      (node (ref "U6") (pin "3") (pinfunction "6_3") (pintype "passive"))
    )
    (net (code "49") (name "/Sensor_7") (class "Default")
      (node (ref "U6") (pin "2") (pinfunction "7_2") (pintype "passive"))
    )
    (net (code "50") (name "/TX") (class "Default")
      (node (ref "RX/TX") (pin "2") (pinfunction "2_2") (pintype "passive"))
      (node (ref "U3") (pin "7") (pinfunction "IO17_7") (pintype "passive"))
    )
    (net (code "51") (name "/V5 Motor") (class "Default")
      (node (ref "*") (pin "20") (pinfunction "VCC_20") (pintype "power_in"))
      (node (ref "C1") (pin "1") (pintype "passive"))
      (node (ref "C6") (pin "+") (pinfunction "+_+") (pintype "passive"))
      (node (ref "F1") (pin "2") (pinfunction "2_2") (pintype "passive"))
      (node (ref "R24") (pin "2") (pinfunction "2_2") (pintype "passive"))
    )
    (net (code "52") (name "/VCC") (class "Default")
      (node (ref "*") (pin "13") (pinfunction "VM2_13") (pintype "power_in"))
      (node (ref "*") (pin "14") (pinfunction "VM3_14") (pintype "power_in"))
      (node (ref "*") (pin "24") (pinfunction "VM1_24") (pintype "power_in"))
      (node (ref "C12") (pin "1") (pintype "passive"))
      (node (ref "C15") (pin "1") (pintype "passive"))
      (node (ref "C3") (pin "2") (pinfunction "C2_2") (pintype "passive"))
      (node (ref "C4") (pin "1") (pinfunction "1_1") (pintype "passive"))
      (node (ref "C5") (pin "1") (pinfunction "1_1") (pintype "passive"))
      (node (ref "C7") (pin "1") (pintype "passive"))
      (node (ref "F2") (pin "1") (pinfunction "1_1") (pintype "passive"))
      (node (ref "IC1_5v") (pin "1") (pinfunction "IN_1") (pintype "power_in"))
      (node (ref "R21") (pin "2") (pinfunction "R2_2") (pintype "passive"))
      (node (ref "U1") (pin "8") (pinfunction "8_8") (pintype "passive"))
      (node (ref "U2_3.3v") (pin "3") (pinfunction "IN_3") (pintype "power_in"))
    )
    (net (code "53") (name "/Vin_BAT") (class "Default")
      (node (ref "BAT") (pin "2") (pinfunction "2_2") (pintype "passive"))
      (node (ref "Q5") (pin "3") (pinfunction "E_3") (pintype "passive"))
      (node (ref "Q6") (pin "3") (pinfunction "E_3") (pintype "passive"))
      (node (ref "R1") (pin "2") (pintype "passive"))
      (node (ref "R10") (pin "1") (pintype "passive"))
    )
    (net (code "54") (name "/Vin_Charg") (class "Default")
      (node (ref "Charger") (pin "1") (pinfunction "1_1") (pintype "passive"))
      (node (ref "Q6") (pin "2") (pinfunction "C_2") (pintype "passive"))
      (node (ref "R1") (pin "1") (pintype "passive"))
      (node (ref "R2") (pin "2") (pinfunction "R2_2") (pintype "passive"))
      (node (ref "R6") (pin "2") (pinfunction "2_2") (pintype "passive"))
    )
    (net (code "55") (name "/X1") (class "Default")
      (node (ref "U4") (pin "1") (pinfunction "X1_1") (pintype "passive"))
      (node (ref "Y1") (pin "1") (pinfunction "OSC1_1") (pintype "passive"))
    )
    (net (code "56") (name "/X2") (class "Default")
      (node (ref "U4") (pin "2") (pinfunction "X2_2") (pintype "passive"))
      (node (ref "Y1") (pin "2") (pinfunction "OSC2_2") (pintype "passive"))
    )
    (net (code "57") (name "GNDD") (class "Default")
      (node (ref "*") (pin "10") (pinfunction "PGND2@2_10") (pintype "passive"))
      (node (ref "*") (pin "18") (pinfunction "GND_18") (pintype "passive"))
      (node (ref "*") (pin "3") (pinfunction "PGND1@1_3") (pintype "passive"))
      (node (ref "*") (pin "4") (pinfunction "PGND1@2_4") (pintype "passive"))
      (node (ref "*") (pin "9") (pinfunction "PGND2@1_9") (pintype "passive"))
      (node (ref "BT1") (pin "2") (pinfunction "-_2") (pintype "passive"))
      (node (ref "C1") (pin "2") (pintype "passive"))
      (node (ref "C10") (pin "2") (pinfunction "2_2") (pintype "passive"))
      (node (ref "C12") (pin "2") (pintype "passive"))
      (node (ref "C13") (pin "1") (pinfunction "C1_1") (pintype "passive"))
      (node (ref "C14") (pin "2") (pinfunction "2_2") (pintype "passive"))
      (node (ref "C15") (pin "2") (pintype "passive"))
      (node (ref "C17") (pin "1") (pinfunction "C1_1") (pintype "passive"))
      (node (ref "C18") (pin "2") (pinfunction "C2_2") (pintype "passive"))
      (node (ref "C2") (pin "1") (pinfunction "C1_1") (pintype "passive"))
      (node (ref "C21") (pin "1") (pinfunction "C1_1") (pintype "passive"))
      (node (ref "C22") (pin "2") (pinfunction "C2_2") (pintype "passive"))
      (node (ref "C3") (pin "1") (pinfunction "C1_1") (pintype "passive"))
      (node (ref "C4") (pin "2") (pinfunction "2_2") (pintype "passive"))
      (node (ref "C5") (pin "2") (pinfunction "2_2") (pintype "passive"))
      (node (ref "C6") (pin "-") (pinfunction "-_-") (pintype "passive"))
      (node (ref "C7") (pin "2") (pintype "passive"))
      (node (ref "D2") (pin "A") (pinfunction "A_A") (pintype "passive"))
      (node (ref "D3") (pin "A") (pinfunction "A_A") (pintype "passive"))
      (node (ref "D4") (pin "A") (pinfunction "A_A") (pintype "passive"))
      (node (ref "D5") (pin "3") (pinfunction "3_3") (pintype "passive"))
      (node (ref "IC1_5v") (pin "4") (pinfunction "GND_4") (pintype "power_in"))
      (node (ref "LED-3.3V") (pin "K") (pinfunction "K_K") (pintype "passive"))
      (node (ref "LED-VCC") (pin "K") (pinfunction "K_K") (pintype "passive"))
      (node (ref "LED_-Charg") (pin "K") (pinfunction "K_K") (pintype "passive"))
      (node (ref "LED_5V") (pin "K") (pinfunction "K_K") (pintype "passive"))
      (node (ref "MPU6050") (pin "2") (pinfunction "2_2") (pintype "passive"))
      (node (ref "OLED") (pin "1") (pinfunction "1_1") (pintype "passive"))
      (node (ref "Q1") (pin "E") (pintype "passive"))
      (node (ref "Q2") (pin "E") (pintype "passive"))
      (node (ref "Q3") (pin "E") (pintype "passive"))
      (node (ref "Q4") (pin "E") (pintype "passive"))
      (node (ref "R16") (pin "2") (pinfunction "2_2") (pintype "passive"))
      (node (ref "R17") (pin "2") (pinfunction "2_2") (pintype "passive"))
      (node (ref "R18") (pin "2") (pinfunction "2_2") (pintype "passive"))
      (node (ref "R19") (pin "2") (pinfunction "2_2") (pintype "passive"))
      (node (ref "R20") (pin "2") (pinfunction "2_2") (pintype "passive"))
      (node (ref "R33") (pin "2") (pinfunction "2_2") (pintype "passive"))
      (node (ref "R34") (pin "2") (pinfunction "2_2") (pintype "passive"))
      (node (ref "R35") (pin "2") (pinfunction "2_2") (pintype "passive"))
      (node (ref "R38") (pin "2") (pinfunction "2_2") (pintype "passive"))
      (node (ref "R39") (pin "2") (pinfunction "2_2") (pintype "passive"))
      (node (ref "R40") (pin "2") (pinfunction "2_2") (pintype "passive"))
      (node (ref "R41") (pin "2") (pinfunction "2_2") (pintype "passive"))
      (node (ref "R42") (pin "1") (pinfunction "1_1") (pintype "passive"))
      (node (ref "R43") (pin "1") (pinfunction "1_1") (pintype "passive"))
      (node (ref "R44") (pin "1") (pinfunction "1_1") (pintype "passive"))
      (node (ref "R45") (pin "2") (pinfunction "2_2") (pintype "passive"))
      (node (ref "R46") (pin "1") (pinfunction "1_1") (pintype "passive"))
      (node (ref "R47") (pin "2") (pinfunction "2_2") (pintype "passive"))
      (node (ref "R5") (pin "2") (pinfunction "2_2") (pintype "passive"))
      (node (ref "RX/TX") (pin "1") (pinfunction "1_1") (pintype "passive"))
      (node (ref "S2") (pin "1") (pintype "passive"))
      (node (ref "S3") (pin "1") (pintype "passive"))
      (node (ref "S4") (pin "1") (pintype "passive"))
      (node (ref "U1") (pin "2") (pinfunction "2_2") (pintype "passive"))
      (node (ref "U1") (pin "3") (pinfunction "3_3") (pintype "passive"))
      (node (ref "U1") (pin "6") (pinfunction "6_6") (pintype "passive"))
      (node (ref "U1") (pin "7") (pinfunction "7_7") (pintype "passive"))
      (node (ref "U2_3.3v") (pin "1") (pinfunction "GND_1") (pintype "power_in"))
      (node (ref "U3") (pin "2") (pinfunction "GND_2") (pintype "passive"))
      (node (ref "U3") (pin "29") (pinfunction "GND1_29") (pintype "passive"))
      (node (ref "U4") (pin "4") (pinfunction "GND_4") (pintype "passive"))
      (node (ref "U5") (pin "7") (pinfunction "GND_7") (pintype "passive"))
      (node (ref "U6") (pin "12") (pinfunction "VSS_12") (pintype "passive"))
      (node (ref "U6") (pin "15") (pinfunction "INHIBT_15") (pintype "passive"))
      (node (ref "U7") (pin "7") (pinfunction "GND_7") (pintype "passive"))
    )
    (net (code "58") (name "Net-(*-STBY)") (class "Default")
      (node (ref "*") (pin "19") (pinfunction "STBY_19") (pintype "input"))
      (node (ref "R24") (pin "1") (pinfunction "1_1") (pintype "passive"))
    )
    (net (code "59") (name "Net-(BAT-Pad1)") (class "Default")
      (node (ref "BAT") (pin "1") (pinfunction "1_1") (pintype "passive"))
      (node (ref "D4") (pin "K") (pinfunction "K_K") (pintype "passive"))
    )
    (net (code "60") (name "Net-(BT1-+)") (class "Default")
      (node (ref "BT1") (pin "1") (pinfunction "+_1") (pintype "passive"))
      (node (ref "U4") (pin "3") (pinfunction "VBAT_3") (pintype "passive"))
    )
    (net (code "61") (name "Net-(C2-C2)") (class "Default")
      (node (ref "C2") (pin "2") (pinfunction "C2_2") (pintype "passive"))
      (node (ref "F1") (pin "1") (pinfunction "1_1") (pintype "passive"))
      (node (ref "U1") (pin "1") (pinfunction "1_1") (pintype "passive"))
    )
    (net (code "62") (name "Net-(Charger-Pad2)") (class "Default")
      (node (ref "Charger") (pin "2") (pinfunction "2_2") (pintype "passive"))
      (node (ref "Charger") (pin "3") (pinfunction "3_3") (pintype "passive"))
      (node (ref "D2") (pin "K") (pinfunction "K_K") (pintype "passive"))
    )
    (net (code "63") (name "Net-(D1-Pad1)") (class "Default")
      (node (ref "D1") (pin "1") (pinfunction "1_1") (pintype "passive"))
      (node (ref "Q4") (pin "C") (pintype "passive"))
    )
    (net (code "64") (name "Net-(D1-Pad2)") (class "Default")
      (node (ref "D1") (pin "2") (pinfunction "2_2") (pintype "passive"))
      (node (ref "Q2") (pin "C") (pintype "passive"))
    )
    (net (code "65") (name "Net-(D1-Pad3)") (class "Default")
      (node (ref "D1") (pin "3") (pinfunction "3_3") (pintype "passive"))
      (node (ref "Q1") (pin "C") (pintype "passive"))
    )
    (net (code "66") (name "Net-(F2-Pad2)") (class "Default")
      (node (ref "F2") (pin "2") (pinfunction "2_2") (pintype "passive"))
      (node (ref "S1") (pin "2") (pinfunction "2_2") (pintype "passive"))
    )
    (net (code "67") (name "Net-(IC1_5v-OUT)") (class "Default")
      (node (ref "F3") (pin "2") (pinfunction "2_2") (pintype "passive"))
      (node (ref "IC1_5v") (pin "3") (pinfunction "OUT_3") (pintype "power_in"))
    )
    (net (code "68") (name "Net-(LED1-PadK)") (class "Default")
      (node (ref "LED1") (pin "K") (pinfunction "K_K") (pintype "passive"))
      (node (ref "R38") (pin "1") (pinfunction "1_1") (pintype "passive"))
    )
    (net (code "69") (name "Net-(LED2-PadK)") (class "Default")
      (node (ref "LED2") (pin "K") (pinfunction "K_K") (pintype "passive"))
      (node (ref "R39") (pin "1") (pinfunction "1_1") (pintype "passive"))
    )
    (net (code "70") (name "Net-(LED3-PadK)") (class "Default")
      (node (ref "LED3") (pin "K") (pinfunction "K_K") (pintype "passive"))
      (node (ref "R45") (pin "1") (pinfunction "1_1") (pintype "passive"))
    )
    (net (code "71") (name "Net-(LED4-PadK)") (class "Default")
      (node (ref "LED4") (pin "K") (pinfunction "K_K") (pintype "passive"))
      (node (ref "R47") (pin "1") (pinfunction "1_1") (pintype "passive"))
    )
    (net (code "72") (name "Net-(MPU6050-Pad7)") (class "Default")
      (node (ref "MPU6050") (pin "7") (pinfunction "7_7") (pintype "passive"))
      (node (ref "R25") (pin "2") (pinfunction "2_2") (pintype "passive"))
    )
    (net (code "73") (name "Net-(Q1-PadB)") (class "Default")
      (node (ref "Q1") (pin "B") (pintype "passive"))
      (node (ref "R11") (pin "2") (pinfunction "2_2") (pintype "passive"))
    )
    (net (code "74") (name "Net-(Q2-PadB)") (class "Default")
      (node (ref "Q2") (pin "B") (pintype "passive"))
      (node (ref "R12") (pin "2") (pinfunction "2_2") (pintype "passive"))
    )
    (net (code "75") (name "Net-(Q3-PadB)") (class "Default")
      (node (ref "Q3") (pin "B") (pintype "passive"))
      (node (ref "R13") (pin "1") (pinfunction "1_1") (pintype "passive"))
    )
    (net (code "76") (name "Net-(Q4-PadB)") (class "Default")
      (node (ref "Q4") (pin "B") (pintype "passive"))
      (node (ref "R14") (pin "2") (pinfunction "2_2") (pintype "passive"))
    )
    (net (code "77") (name "Net-(Q5-B)") (class "Default")
      (node (ref "Q5") (pin "1") (pinfunction "B_1") (pintype "passive"))
      (node (ref "R9") (pin "1") (pinfunction "1_1") (pintype "passive"))
    )
    (net (code "78") (name "Net-(Q5-C)") (class "Default")
      (node (ref "Q5") (pin "2") (pinfunction "C_2") (pintype "passive"))
      (node (ref "R10") (pin "2") (pintype "passive"))
      (node (ref "S1") (pin "3") (pinfunction "3_3") (pintype "passive"))
    )
    (net (code "79") (name "Net-(Q6-B)") (class "Default")
      (node (ref "Q6") (pin "1") (pinfunction "B_1") (pintype "passive"))
      (node (ref "R15") (pin "1") (pinfunction "1_1") (pintype "passive"))
    )
    (net (code "80") (name "Net-(Q7-PadB)") (class "Default")
      (node (ref "Q7") (pin "B") (pintype "passive"))
      (node (ref "R37") (pin "1") (pinfunction "1_1") (pintype "passive"))
    )
    (net (code "81") (name "Net-(R2-R1)") (class "Default")
      (node (ref "LED_-Charg") (pin "A") (pinfunction "A_A") (pintype "passive"))
      (node (ref "R2") (pin "1") (pinfunction "R1_1") (pintype "passive"))
    )
    (net (code "82") (name "Net-(R3-R2)") (class "Default")
      (node (ref "D1") (pin "4") (pinfunction "4_4") (pintype "passive"))
      (node (ref "R3") (pin "2") (pinfunction "R2_2") (pintype "passive"))
    )
    (net (code "83") (name "Net-(R4-R2)") (class "Default")
      (node (ref "D1") (pin "5") (pinfunction "5_5") (pintype "passive"))
      (node (ref "R4") (pin "2") (pinfunction "R2_2") (pintype "passive"))
    )
    (net (code "84") (name "Net-(R8-R2)") (class "Default")
      (node (ref "D1") (pin "6") (pinfunction "6_6") (pintype "passive"))
      (node (ref "R8") (pin "2") (pinfunction "R2_2") (pintype "passive"))
    )
    (net (code "85") (name "Net-(R21-R1)") (class "Default")
      (node (ref "LED-VCC") (pin "A") (pinfunction "A_A") (pintype "passive"))
      (node (ref "R21") (pin "1") (pinfunction "R1_1") (pintype "passive"))
    )
    (net (code "86") (name "Net-(R26-R1)") (class "Default")
      (node (ref "LED-3.3V") (pin "A") (pinfunction "A_A") (pintype "passive"))
      (node (ref "R26") (pin "1") (pinfunction "R1_1") (pintype "passive"))
    )
    (net (code "87") (name "Net-(R28-R1)") (class "Default")
      (node (ref "LED_5V") (pin "A") (pinfunction "A_A") (pintype "passive"))
      (node (ref "R28") (pin "1") (pinfunction "R1_1") (pintype "passive"))
    )
    (net (code "88") (name "Net-(R32-R2)") (class "Default")
      (node (ref "R32") (pin "2") (pinfunction "R2_2") (pintype "passive"))
      (node (ref "U4") (pin "7") (pinfunction "SQW/OUT_7") (pintype "passive"))
    )
    (net (code "89") (name "Net-(R34-Pad1)") (class "Default")
      (node (ref "R34") (pin "1") (pinfunction "1_1") (pintype "passive"))
      (node (ref "R36") (pin "1") (pinfunction "1_1") (pintype "passive"))
      (node (ref "R37") (pin "2") (pinfunction "2_2") (pintype "passive"))
    )
    (net (code "90") (name "Net-(SP1-+)") (class "Default")
      (node (ref "R7") (pin "2") (pinfunction "2_2") (pintype "passive"))
      (node (ref "SP1") (pin "1") (pinfunction "+_1") (pintype "passive"))
    )
    (net (code "91") (name "Net-(SP1--)") (class "Default")
      (node (ref "Q3") (pin "C") (pintype "passive"))
      (node (ref "SP1") (pin "2") (pinfunction "-_2") (pintype "passive"))
    )
    (net (code "92") (name "Net-(U2_3.3v-OUT)") (class "Default")
      (node (ref "F4") (pin "2") (pinfunction "2_2") (pintype "passive"))
      (node (ref "U2_3.3v") (pin "2") (pinfunction "OUT_2") (pintype "power_in"))
      (node (ref "U2_3.3v") (pin "4") (pinfunction "TAB_4") (pintype "power_in"))
    )
    (net (code "93") (name "Net-(U6-D)") (class "Default")
      (node (ref "R46") (pin "2") (pinfunction "2_2") (pintype "passive"))
      (node (ref "U6") (pin "13") (pinfunction "D_13") (pintype "passive"))
    )
    (net (code "94") (name "unconnected-(MPU6050-Pad5)") (class "Default")
      (node (ref "MPU6050") (pin "5") (pinfunction "5_5") (pintype "passive+no_connect"))
    )
    (net (code "95") (name "unconnected-(MPU6050-Pad6)") (class "Default")
      (node (ref "MPU6050") (pin "6") (pinfunction "6_6") (pintype "passive+no_connect"))
    )
    (net (code "96") (name "unconnected-(MPU6050-Pad8)") (class "Default")
      (node (ref "MPU6050") (pin "8") (pinfunction "8_8") (pintype "passive+no_connect"))
    )
    (net (code "97") (name "unconnected-(S1-Pad1)") (class "Default")
      (node (ref "S1") (pin "1") (pinfunction "1_1") (pintype "passive"))
    )
    (net (code "98") (name "unconnected-(U1-5-Pad4)") (class "Default")
      (node (ref "U1") (pin "4") (pinfunction "5_4") (pintype "passive+no_connect"))
    )
    (net (code "99") (name "unconnected-(U1-Pad4)") (class "Default")
      (node (ref "U1") (pin "4") (pinfunction "4_4") (pintype "passive+no_connect"))
    )
    (net (code "100") (name "unconnected-(U3-3V3-Pad1)") (class "Default")
      (node (ref "U3") (pin "1") (pinfunction "3V3_1") (pintype "passive+no_connect"))
    )
    (net (code "101") (name "unconnected-(U3-EN-Pad16)") (class "Default")
      (node (ref "U3") (pin "16") (pinfunction "EN_16") (pintype "passive+no_connect"))
    )
    (net (code "102") (name "unconnected-(U3-IO5-Pad8)") (class "Default")
      (node (ref "U3") (pin "8") (pinfunction "IO5_8") (pintype "passive"))
    )
    (net (code "103") (name "unconnected-(U5-2Y-Pad4)") (class "Default")
      (node (ref "U5") (pin "4") (pinfunction "2Y_4") (pintype "output"))
    )
    (net (code "104") (name "unconnected-(U5-6A-Pad13)") (class "Default")
      (node (ref "U5") (pin "13") (pinfunction "6A_13") (pintype "input+no_connect"))
    )
    (net (code "105") (name "unconnected-(U5-6Y-Pad12)") (class "Default")
      (node (ref "U5") (pin "12") (pinfunction "6Y_12") (pintype "output+no_connect"))
    )
    (net (code "106") (name "unconnected-(U6-8-Pad23)") (class "Default")
      (node (ref "U6") (pin "23") (pinfunction "8_23") (pintype "passive+no_connect"))
    )
    (net (code "107") (name "unconnected-(U6-9-Pad22)") (class "Default")
      (node (ref "U6") (pin "22") (pinfunction "9_22") (pintype "passive+no_connect"))
    )
    (net (code "108") (name "unconnected-(U6-10-Pad21)") (class "Default")
      (node (ref "U6") (pin "21") (pinfunction "10_21") (pintype "passive+no_connect"))
    )
    (net (code "109") (name "unconnected-(U6-11-Pad20)") (class "Default")
      (node (ref "U6") (pin "20") (pinfunction "11_20") (pintype "passive+no_connect"))
    )
    (net (code "110") (name "unconnected-(U6-12-Pad19)") (class "Default")
      (node (ref "U6") (pin "19") (pinfunction "12_19") (pintype "passive+no_connect"))
    )
    (net (code "111") (name "unconnected-(U6-13-Pad18)") (class "Default")
      (node (ref "U6") (pin "18") (pinfunction "13_18") (pintype "passive+no_connect"))
    )
    (net (code "112") (name "unconnected-(U6-14-Pad17)") (class "Default")
      (node (ref "U6") (pin "17") (pinfunction "14_17") (pintype "passive+no_connect"))
    )
    (net (code "113") (name "unconnected-(U6-15-Pad16)") (class "Default")
      (node (ref "U6") (pin "16") (pinfunction "15_16") (pintype "passive+no_connect"))
    )
    (net (code "114") (name "unconnected-(U7-6A-Pad13)") (class "Default")
      (node (ref "U7") (pin "13") (pinfunction "6A_13") (pintype "input+no_connect"))
    )
    (net (code "115") (name "unconnected-(U7-6Y-Pad12)") (class "Default")
      (node (ref "U7") (pin "12") (pinfunction "6Y_12") (pintype "output+no_connect"))
    )
  )
)
